# PNP.net
KiCad netlist of a schematic drawn in EAGLE
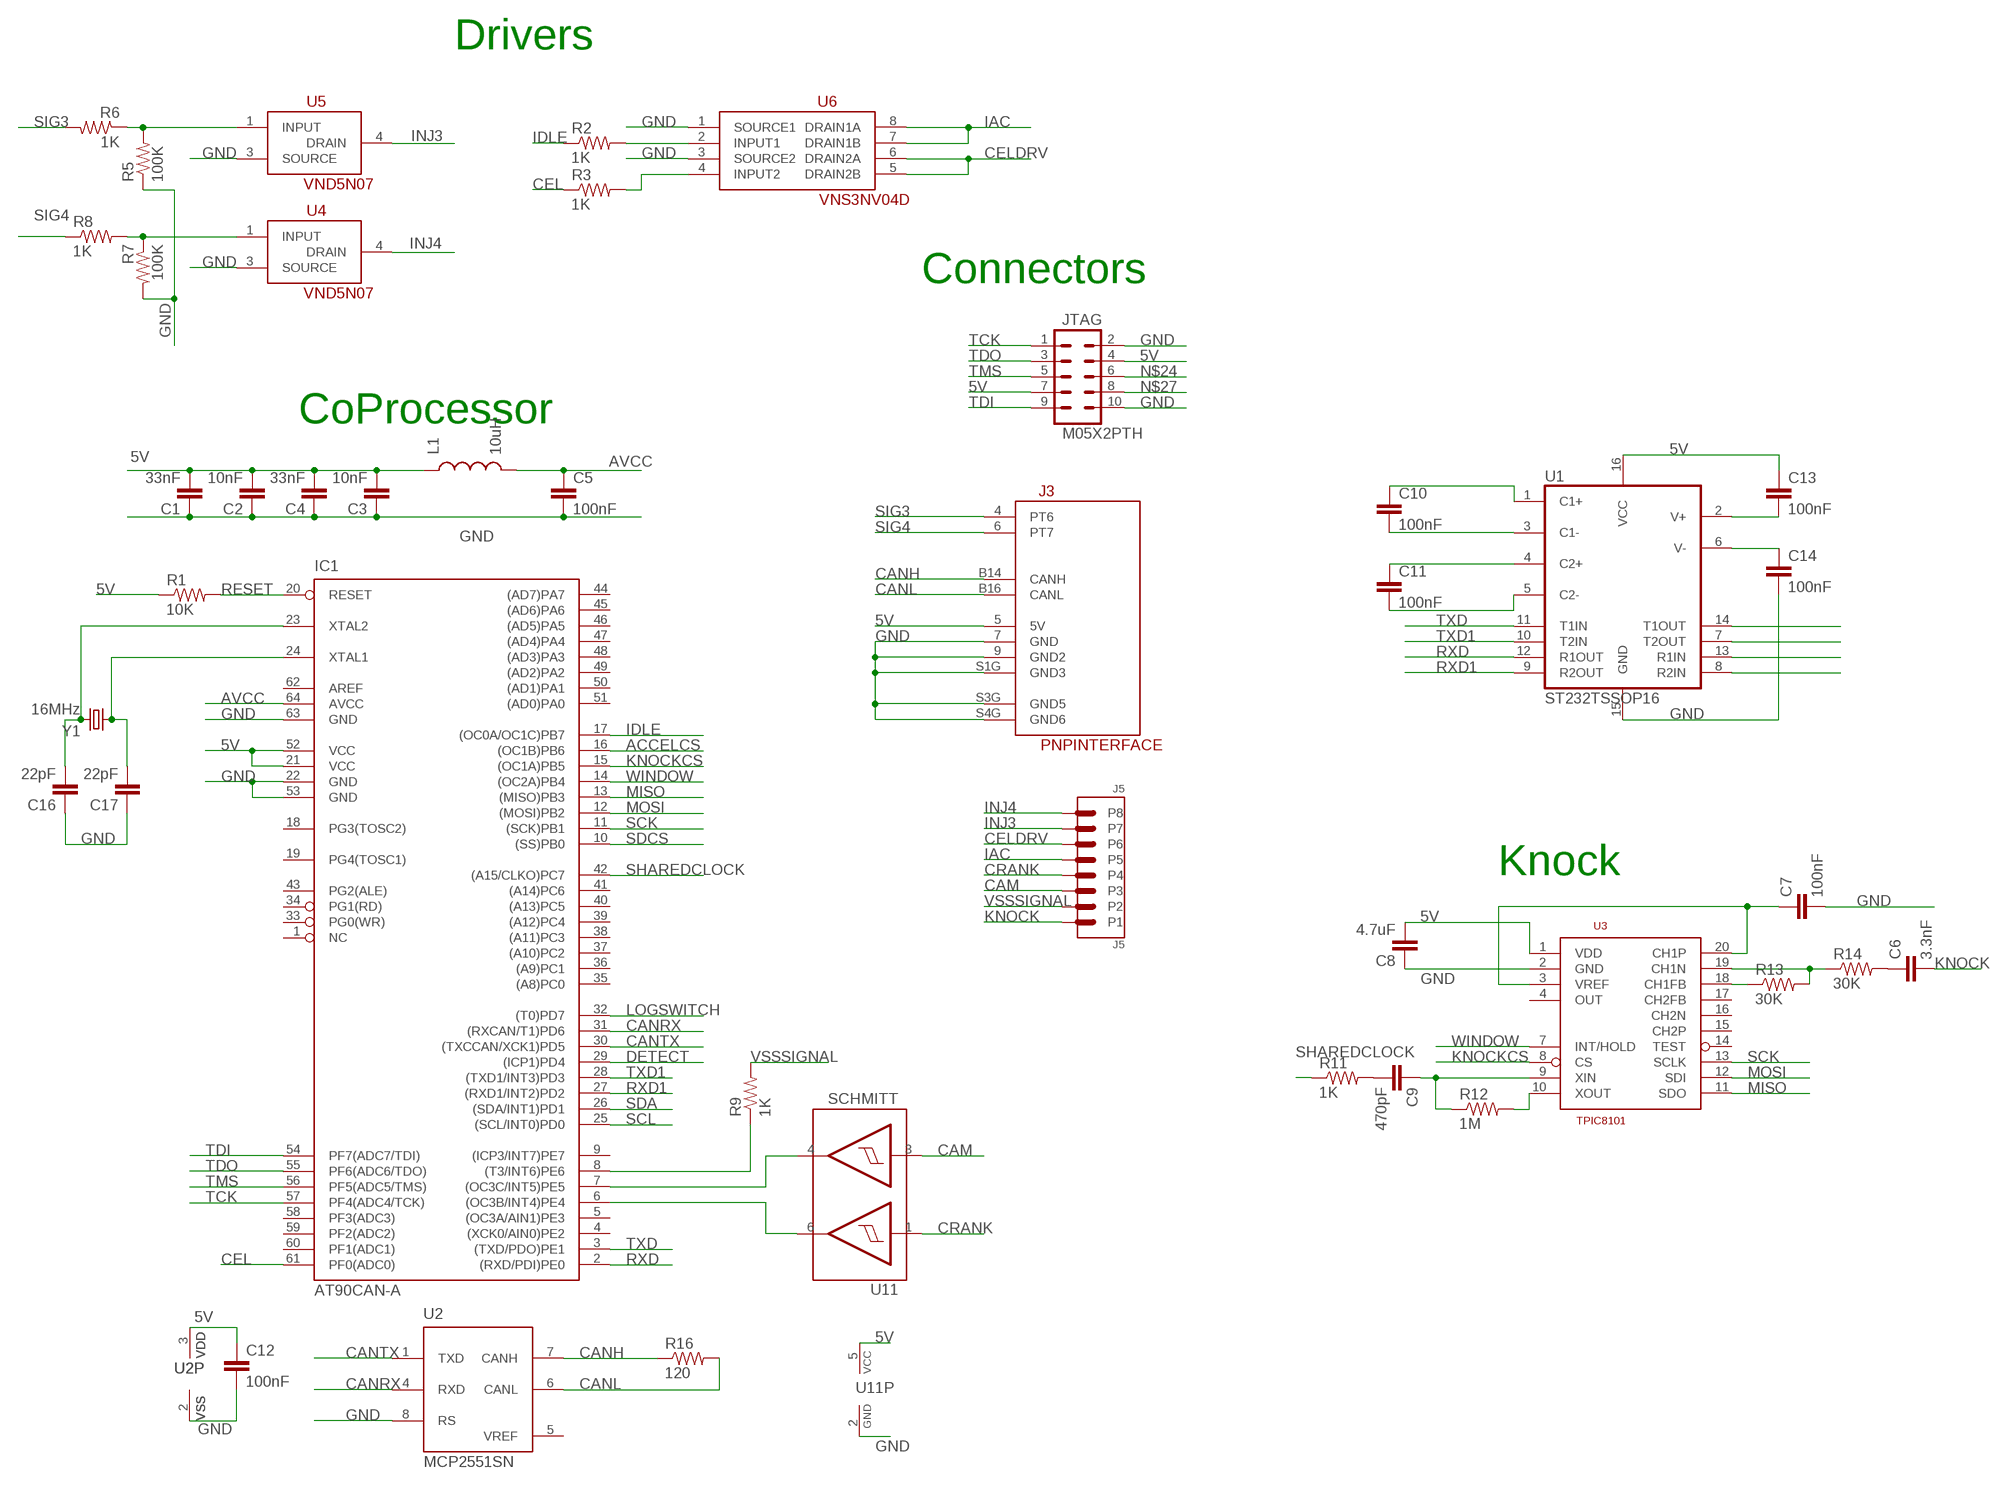
[diagram p0: schematic, sheet 1]

(export (version "E")
  (design (tool "Eeschema 10.0.6"))
  (components
    (comp (ref "C1")
      (value "33nF")
      (footprint "eagle-import:0805")
      (libsource (lib "eagle-import") (part "CAP0805"))
    )
    (comp (ref "C2")
      (value "10nF")
      (footprint "eagle-import:0805")
      (libsource (lib "eagle-import") (part "CAP0805"))
    )
    (comp (ref "C3")
      (value "10nF")
      (footprint "eagle-import:0805")
      (libsource (lib "eagle-import") (part "CAP0805"))
    )
    (comp (ref "C4")
      (value "33nF")
      (footprint "eagle-import:0805")
      (libsource (lib "eagle-import") (part "CAP0805"))
    )
    (comp (ref "C5")
      (value "100nF")
      (footprint "eagle-import:0805")
      (libsource (lib "eagle-import") (part "CAP0805"))
    )
    (comp (ref "C6")
      (value "3.3nF")
      (footprint "eagle-import:0805")
      (libsource (lib "eagle-import") (part "CAP0805"))
    )
    (comp (ref "C7")
      (value "100nF")
      (footprint "eagle-import:0805")
      (libsource (lib "eagle-import") (part "CAP0805"))
    )
    (comp (ref "C8")
      (value "4.7uF")
      (footprint "eagle-import:0805")
      (libsource (lib "eagle-import") (part "CAP0805"))
    )
    (comp (ref "C9")
      (value "470pF")
      (footprint "eagle-import:0805")
      (libsource (lib "eagle-import") (part "CAP0805"))
    )
    (comp (ref "C10")
      (value "100nF")
      (footprint "eagle-import:0805")
      (libsource (lib "eagle-import") (part "CAP0805"))
    )
    (comp (ref "C11")
      (value "100nF")
      (footprint "eagle-import:0805")
      (libsource (lib "eagle-import") (part "CAP0805"))
    )
    (comp (ref "C12")
      (value "100nF")
      (footprint "eagle-import:0805")
      (libsource (lib "eagle-import") (part "CAP0805"))
    )
    (comp (ref "C13")
      (value "100nF")
      (footprint "eagle-import:0805")
      (libsource (lib "eagle-import") (part "CAP0805"))
    )
    (comp (ref "C14")
      (value "100nF")
      (footprint "eagle-import:0805")
      (libsource (lib "eagle-import") (part "CAP0805"))
    )
    (comp (ref "C16")
      (value "22pF")
      (footprint "eagle-import:0805")
      (libsource (lib "eagle-import") (part "CAP0805"))
    )
    (comp (ref "C17")
      (value "22pF")
      (footprint "eagle-import:0805")
      (libsource (lib "eagle-import") (part "CAP0805"))
    )
    (comp (ref "IC1")
      (value "AT90CAN-A")
      (footprint "eagle-import:TQFP64")
      (fields (field (name "MPN") "AT90CAN32-16AU"))
      (libsource (lib "eagle-import") (part "AT90CAN-A"))
    )
    (comp (ref "J3")
      (value "PNPINTERFACE")
      (footprint "eagle-import:PNPBOARD")
      (libsource (lib "eagle-import") (part "PNPINTERFACE"))
    )
    (comp (ref "J5")
      (value "J5")
      (footprint "eagle-import:TERMINAL8")
      (libsource (lib "eagle-import") (part "TERMINAL8"))
    )
    (comp (ref "JTAG")
      (value "M05X2PTH")
      (footprint "eagle-import:AVR_ICSP")
      (libsource (lib "eagle-import") (part "M05X2PTH"))
    )
    (comp (ref "L1")
      (value "10uH")
      (footprint "eagle-import:1210")
      (libsource (lib "eagle-import") (part "INDUCTOR1210"))
    )
    (comp (ref "R1")
      (value "10K")
      (footprint "eagle-import:0805")
      (libsource (lib "eagle-import") (part "RESISTOR0805-RES"))
    )
    (comp (ref "R2")
      (value "1K")
      (footprint "eagle-import:0805")
      (libsource (lib "eagle-import") (part "RESISTOR0805-RES"))
    )
    (comp (ref "R3")
      (value "1K")
      (footprint "eagle-import:0805")
      (libsource (lib "eagle-import") (part "RESISTOR0805-RES"))
    )
    (comp (ref "R5")
      (value "100K")
      (footprint "eagle-import:0805")
      (libsource (lib "eagle-import") (part "RESISTOR0805-RES"))
    )
    (comp (ref "R6")
      (value "1K")
      (footprint "eagle-import:0805")
      (libsource (lib "eagle-import") (part "RESISTOR0805-RES"))
    )
    (comp (ref "R7")
      (value "100K")
      (footprint "eagle-import:0805")
      (libsource (lib "eagle-import") (part "RESISTOR0805-RES"))
    )
    (comp (ref "R8")
      (value "1K")
      (footprint "eagle-import:0805")
      (libsource (lib "eagle-import") (part "RESISTOR0805-RES"))
    )
    (comp (ref "R9")
      (value "1K")
      (footprint "eagle-import:0805")
      (libsource (lib "eagle-import") (part "RESISTOR0805-RES"))
    )
    (comp (ref "R11")
      (value "1K")
      (footprint "eagle-import:0805")
      (libsource (lib "eagle-import") (part "RESISTOR0805-RES"))
    )
    (comp (ref "R12")
      (value "1M")
      (footprint "eagle-import:0805")
      (libsource (lib "eagle-import") (part "RESISTOR0805-RES"))
    )
    (comp (ref "R13")
      (value "30K")
      (footprint "eagle-import:0805")
      (libsource (lib "eagle-import") (part "RESISTOR0805-RES"))
    )
    (comp (ref "R14")
      (value "30K")
      (footprint "eagle-import:0805")
      (libsource (lib "eagle-import") (part "RESISTOR0805-RES"))
    )
    (comp (ref "R16")
      (value "120")
      (footprint "eagle-import:0805")
      (libsource (lib "eagle-import") (part "RESISTOR0805-RES"))
    )
    (comp (ref "U1")
      (value "ST232TSSOP16")
      (footprint "eagle-import:TSSOP16")
      (libsource (lib "eagle-import") (part "ST232TSSOP16"))
    )
    (comp (ref "U2")
      (value "MCP2551SN")
      (footprint "eagle-import:SO8")
      (libsource (lib "eagle-import") (part "MCP2551SN"))
    )
    (comp (ref "U3")
      (value "TPIC8101")
      (footprint "eagle-import:SO-20DW")
      (libsource (lib "eagle-import") (part "TPIC8101"))
    )
    (comp (ref "U4")
      (value "VND5N07")
      (footprint "eagle-import:DPAK")
      (libsource (lib "eagle-import") (part "VND5N07"))
    )
    (comp (ref "U5")
      (value "VND5N07")
      (footprint "eagle-import:DPAK")
      (libsource (lib "eagle-import") (part "VND5N07"))
    )
    (comp (ref "U6")
      (value "VNS3NV04D")
      (footprint "eagle-import:SO8")
      (libsource (lib "eagle-import") (part "VNS3NV04D"))
    )
    (comp (ref "U11")
      (value "SCHMITT")
      (footprint "eagle-import:TSOP6")
      (libsource (lib "eagle-import") (part "SCHMITTTSOP"))
    )
    (comp (ref "Y1")
      (value "16MHz")
      (footprint "eagle-import:SM2-CRYSTAL-7ASERIES")
      (libsource (lib "eagle-import") (part "CRYSTAL"))
    )
  )
  (nets
    (net (code "1") (name "/5V") (class "Default")
      (node (ref "C1") (pin "2") (pinfunction "2_2") (pintype "passive"))
      (node (ref "C12") (pin "1") (pinfunction "1_1") (pintype "passive"))
      (node (ref "C13") (pin "1") (pinfunction "1_1") (pintype "passive"))
      (node (ref "C2") (pin "2") (pinfunction "2_2") (pintype "passive"))
      (node (ref "C3") (pin "2") (pinfunction "2_2") (pintype "passive"))
      (node (ref "C4") (pin "2") (pinfunction "2_2") (pintype "passive"))
      (node (ref "C8") (pin "2") (pinfunction "2_2") (pintype "passive"))
      (node (ref "IC1") (pin "21") (pinfunction "VCC_21") (pintype "power_in"))
      (node (ref "IC1") (pin "52") (pinfunction "VCC_52") (pintype "power_in"))
      (node (ref "J3") (pin "5") (pinfunction "5V_5") (pintype "power_in"))
      (node (ref "JTAG") (pin "4") (pinfunction "4_4") (pintype "passive"))
      (node (ref "JTAG") (pin "7") (pinfunction "7_7") (pintype "passive"))
      (node (ref "L1") (pin "1") (pinfunction "1_1") (pintype "passive"))
      (node (ref "R1") (pin "1") (pinfunction "1_1") (pintype "passive"))
      (node (ref "U1") (pin "16") (pinfunction "VCC_16") (pintype "bidirectional"))
      (node (ref "U11") (pin "5") (pinfunction "VCC_5") (pintype "power_in"))
      (node (ref "U2") (pin "3") (pinfunction "VDD_3") (pintype "power_in"))
      (node (ref "U3") (pin "1") (pinfunction "VDD_1") (pintype "power_in"))
    )
    (net (code "2") (name "/ACCELCS") (class "Default")
      (node (ref "IC1") (pin "16") (pinfunction "(OC1B)PB6_16") (pintype "bidirectional"))
    )
    (net (code "3") (name "/AVCC") (class "Default")
      (node (ref "C5") (pin "1") (pinfunction "1_1") (pintype "passive"))
      (node (ref "IC1") (pin "64") (pinfunction "AVCC_64") (pintype "power_in"))
      (node (ref "L1") (pin "2") (pinfunction "2_2") (pintype "passive"))
    )
    (net (code "4") (name "/CAM") (class "Default")
      (node (ref "J5") (pin "P3") (pinfunction "P3_P3") (pintype "passive"))
      (node (ref "U11") (pin "3") (pinfunction "I2_3") (pintype "input"))
    )
    (net (code "5") (name "/CANH") (class "Default")
      (node (ref "J3") (pin "B14") (pinfunction "CANH_B14") (pintype "bidirectional"))
      (node (ref "R16") (pin "1") (pinfunction "1_1") (pintype "passive"))
      (node (ref "U2") (pin "7") (pinfunction "CANH_7") (pintype "bidirectional"))
    )
    (net (code "6") (name "/CANL") (class "Default")
      (node (ref "J3") (pin "B16") (pinfunction "CANL_B16") (pintype "bidirectional"))
      (node (ref "R16") (pin "2") (pinfunction "2_2") (pintype "passive"))
      (node (ref "U2") (pin "6") (pinfunction "CANL_6") (pintype "bidirectional"))
    )
    (net (code "7") (name "/CANRX") (class "Default")
      (node (ref "IC1") (pin "31") (pinfunction "(RXCAN/T1)PD6_31") (pintype "bidirectional"))
      (node (ref "U2") (pin "4") (pinfunction "RXD_4") (pintype "output"))
    )
    (net (code "8") (name "/CANTX") (class "Default")
      (node (ref "IC1") (pin "30") (pinfunction "(TXCCAN/XCK1)PD5_30") (pintype "bidirectional"))
      (node (ref "U2") (pin "1") (pinfunction "TXD_1") (pintype "input"))
    )
    (net (code "9") (name "/CEL") (class "Default")
      (node (ref "IC1") (pin "61") (pinfunction "PF0(ADC0)_61") (pintype "bidirectional"))
      (node (ref "R3") (pin "1") (pinfunction "1_1") (pintype "passive"))
    )
    (net (code "10") (name "/CELDRV") (class "Default")
      (node (ref "J5") (pin "P6") (pinfunction "P6_P6") (pintype "passive"))
      (node (ref "U6") (pin "5") (pinfunction "DRAIN2B_5") (pintype "bidirectional"))
      (node (ref "U6") (pin "6") (pinfunction "DRAIN2A_6") (pintype "bidirectional"))
    )
    (net (code "11") (name "/CRANK") (class "Default")
      (node (ref "J5") (pin "P4") (pinfunction "P4_P4") (pintype "passive"))
      (node (ref "U11") (pin "1") (pinfunction "I1_1") (pintype "input"))
    )
    (net (code "12") (name "/DETECT") (class "Default")
      (node (ref "IC1") (pin "29") (pinfunction "(ICP1)PD4_29") (pintype "bidirectional"))
    )
    (net (code "13") (name "/GND") (class "Default")
      (node (ref "C1") (pin "1") (pinfunction "1_1") (pintype "passive"))
      (node (ref "C12") (pin "2") (pinfunction "2_2") (pintype "passive"))
      (node (ref "C14") (pin "2") (pinfunction "2_2") (pintype "passive"))
      (node (ref "C16") (pin "1") (pinfunction "1_1") (pintype "passive"))
      (node (ref "C17") (pin "1") (pinfunction "1_1") (pintype "passive"))
      (node (ref "C2") (pin "1") (pinfunction "1_1") (pintype "passive"))
      (node (ref "C3") (pin "1") (pinfunction "1_1") (pintype "passive"))
      (node (ref "C4") (pin "1") (pinfunction "1_1") (pintype "passive"))
      (node (ref "C5") (pin "2") (pinfunction "2_2") (pintype "passive"))
      (node (ref "C7") (pin "2") (pinfunction "2_2") (pintype "passive"))
      (node (ref "C8") (pin "1") (pinfunction "1_1") (pintype "passive"))
      (node (ref "IC1") (pin "22") (pinfunction "GND_22") (pintype "power_in"))
      (node (ref "IC1") (pin "53") (pinfunction "GND_53") (pintype "power_in"))
      (node (ref "IC1") (pin "63") (pinfunction "GND_63") (pintype "power_in"))
      (node (ref "J3") (pin "7") (pinfunction "GND_7") (pintype "power_in"))
      (node (ref "J3") (pin "9") (pinfunction "GND2_9") (pintype "passive"))
      (node (ref "J3") (pin "S1G") (pinfunction "GND3_S1G") (pintype "passive"))
      (node (ref "J3") (pin "S3G") (pinfunction "GND5_S3G") (pintype "passive"))
      (node (ref "J3") (pin "S4G") (pinfunction "GND6_S4G") (pintype "passive"))
      (node (ref "JTAG") (pin "10") (pinfunction "10_10") (pintype "passive"))
      (node (ref "JTAG") (pin "2") (pinfunction "2_2") (pintype "passive"))
      (node (ref "R5") (pin "1") (pinfunction "1_1") (pintype "passive"))
      (node (ref "R7") (pin "2") (pinfunction "2_2") (pintype "passive"))
      (node (ref "U1") (pin "15") (pinfunction "GND_15") (pintype "bidirectional"))
      (node (ref "U11") (pin "2") (pinfunction "GND_2") (pintype "power_in"))
      (node (ref "U2") (pin "2") (pinfunction "VSS_2") (pintype "power_in"))
      (node (ref "U2") (pin "8") (pinfunction "RS_8") (pintype "input"))
      (node (ref "U3") (pin "2") (pinfunction "GND_2") (pintype "power_in"))
      (node (ref "U4") (pin "3") (pinfunction "SOURCE_3") (pintype "bidirectional"))
      (node (ref "U5") (pin "3") (pinfunction "SOURCE_3") (pintype "bidirectional"))
      (node (ref "U6") (pin "1") (pinfunction "SOURCE1_1") (pintype "bidirectional"))
      (node (ref "U6") (pin "3") (pinfunction "SOURCE2_3") (pintype "bidirectional"))
    )
    (net (code "14") (name "/IAC") (class "Default")
      (node (ref "J5") (pin "P5") (pinfunction "P5_P5") (pintype "passive"))
      (node (ref "U6") (pin "7") (pinfunction "DRAIN1B_7") (pintype "bidirectional"))
      (node (ref "U6") (pin "8") (pinfunction "DRAIN1A_8") (pintype "bidirectional"))
    )
    (net (code "15") (name "/IDLE") (class "Default")
      (node (ref "IC1") (pin "17") (pinfunction "(OC0A/OC1C)PB7_17") (pintype "bidirectional"))
      (node (ref "R2") (pin "1") (pinfunction "1_1") (pintype "passive"))
    )
    (net (code "16") (name "/INJ3") (class "Default")
      (node (ref "J5") (pin "P7") (pinfunction "P7_P7") (pintype "passive"))
      (node (ref "U5") (pin "4") (pinfunction "DRAIN_4") (pintype "bidirectional"))
    )
    (net (code "17") (name "/INJ4") (class "Default")
      (node (ref "J5") (pin "P8") (pinfunction "P8_P8") (pintype "passive"))
      (node (ref "U4") (pin "4") (pinfunction "DRAIN_4") (pintype "bidirectional"))
    )
    (net (code "18") (name "/KNOCK") (class "Default")
      (node (ref "C6") (pin "2") (pinfunction "2_2") (pintype "passive"))
      (node (ref "J5") (pin "P1") (pinfunction "P1_P1") (pintype "passive"))
    )
    (net (code "19") (name "/KNOCKCS") (class "Default")
      (node (ref "IC1") (pin "15") (pinfunction "(OC1A)PB5_15") (pintype "bidirectional"))
      (node (ref "U3") (pin "8") (pinfunction "CS_8") (pintype "input"))
    )
    (net (code "20") (name "/LOGSWITCH") (class "Default")
      (node (ref "IC1") (pin "32") (pinfunction "(T0)PD7_32") (pintype "bidirectional"))
    )
    (net (code "21") (name "/MISO") (class "Default")
      (node (ref "IC1") (pin "13") (pinfunction "(MISO)PB3_13") (pintype "bidirectional"))
      (node (ref "U3") (pin "11") (pinfunction "SDO_11") (pintype "bidirectional"))
    )
    (net (code "22") (name "/MOSI") (class "Default")
      (node (ref "IC1") (pin "12") (pinfunction "(MOSI)PB2_12") (pintype "bidirectional"))
      (node (ref "U3") (pin "12") (pinfunction "SDI_12") (pintype "input"))
    )
    (net (code "23") (name "/N$24") (class "Default")
      (node (ref "JTAG") (pin "6") (pinfunction "6_6") (pintype "passive"))
    )
    (net (code "24") (name "/N$27") (class "Default")
      (node (ref "JTAG") (pin "8") (pinfunction "8_8") (pintype "passive"))
    )
    (net (code "25") (name "/RESET") (class "Default")
      (node (ref "IC1") (pin "20") (pinfunction "RESET_20") (pintype "input"))
      (node (ref "R1") (pin "2") (pinfunction "2_2") (pintype "passive"))
    )
    (net (code "26") (name "/RXD") (class "Default")
      (node (ref "IC1") (pin "2") (pinfunction "(RXD/PDI)PE0_2") (pintype "bidirectional"))
      (node (ref "U1") (pin "12") (pinfunction "R1OUT_12") (pintype "output"))
    )
    (net (code "27") (name "/RXD1") (class "Default")
      (node (ref "IC1") (pin "27") (pinfunction "(RXD1/INT2)PD2_27") (pintype "bidirectional"))
      (node (ref "U1") (pin "9") (pinfunction "R2OUT_9") (pintype "output"))
    )
    (net (code "28") (name "/SCK") (class "Default")
      (node (ref "IC1") (pin "11") (pinfunction "(SCK)PB1_11") (pintype "bidirectional"))
      (node (ref "U3") (pin "13") (pinfunction "SCLK_13") (pintype "input"))
    )
    (net (code "29") (name "/SCL") (class "Default")
      (node (ref "IC1") (pin "25") (pinfunction "(SCL/INT0)PD0_25") (pintype "bidirectional"))
    )
    (net (code "30") (name "/SDA") (class "Default")
      (node (ref "IC1") (pin "26") (pinfunction "(SDA/INT1)PD1_26") (pintype "bidirectional"))
    )
    (net (code "31") (name "/SDCS") (class "Default")
      (node (ref "IC1") (pin "10") (pinfunction "(SS)PB0_10") (pintype "bidirectional"))
    )
    (net (code "32") (name "/SHAREDCLOCK") (class "Default")
      (node (ref "IC1") (pin "42") (pinfunction "(A15/CLKO)PC7_42") (pintype "output"))
      (node (ref "R11") (pin "1") (pinfunction "1_1") (pintype "passive"))
    )
    (net (code "33") (name "/SIG3") (class "Default")
      (node (ref "J3") (pin "4") (pinfunction "PT6_4") (pintype "input"))
      (node (ref "R6") (pin "2") (pinfunction "2_2") (pintype "passive"))
    )
    (net (code "34") (name "/SIG4") (class "Default")
      (node (ref "J3") (pin "6") (pinfunction "PT7_6") (pintype "input"))
      (node (ref "R8") (pin "1") (pinfunction "1_1") (pintype "passive"))
    )
    (net (code "35") (name "/TCK") (class "Default")
      (node (ref "IC1") (pin "57") (pinfunction "PF4(ADC4/TCK)_57") (pintype "bidirectional"))
      (node (ref "JTAG") (pin "1") (pinfunction "1_1") (pintype "passive"))
    )
    (net (code "36") (name "/TDI") (class "Default")
      (node (ref "IC1") (pin "54") (pinfunction "PF7(ADC7/TDI)_54") (pintype "bidirectional"))
      (node (ref "JTAG") (pin "9") (pinfunction "9_9") (pintype "passive"))
    )
    (net (code "37") (name "/TDO") (class "Default")
      (node (ref "IC1") (pin "55") (pinfunction "PF6(ADC6/TDO)_55") (pintype "bidirectional"))
      (node (ref "JTAG") (pin "3") (pinfunction "3_3") (pintype "passive"))
    )
    (net (code "38") (name "/TMS") (class "Default")
      (node (ref "IC1") (pin "56") (pinfunction "PF5(ADC5/TMS)_56") (pintype "bidirectional"))
      (node (ref "JTAG") (pin "5") (pinfunction "5_5") (pintype "passive"))
    )
    (net (code "39") (name "/TXD") (class "Default")
      (node (ref "IC1") (pin "3") (pinfunction "(TXD/PDO)PE1_3") (pintype "bidirectional"))
      (node (ref "U1") (pin "11") (pinfunction "T1IN_11") (pintype "input"))
    )
    (net (code "40") (name "/TXD1") (class "Default")
      (node (ref "IC1") (pin "28") (pinfunction "(TXD1/INT3)PD3_28") (pintype "bidirectional"))
      (node (ref "U1") (pin "10") (pinfunction "T2IN_10") (pintype "input"))
    )
    (net (code "41") (name "/VSSSIGNAL") (class "Default")
      (node (ref "J5") (pin "P2") (pinfunction "P2_P2") (pintype "passive"))
      (node (ref "R9") (pin "2") (pinfunction "2_2") (pintype "passive"))
    )
    (net (code "42") (name "/WINDOW") (class "Default")
      (node (ref "IC1") (pin "14") (pinfunction "(OC2A)PB4_14") (pintype "bidirectional"))
      (node (ref "U3") (pin "7") (pinfunction "INT/HOLD_7") (pintype "bidirectional"))
    )
    (net (code "43") (name "Net-(C6-Pad1)") (class "Default")
      (node (ref "C6") (pin "1") (pinfunction "1_1") (pintype "passive"))
      (node (ref "R14") (pin "2") (pinfunction "2_2") (pintype "passive"))
    )
    (net (code "44") (name "Net-(C9-Pad2)") (class "Default")
      (node (ref "C9") (pin "2") (pinfunction "2_2") (pintype "passive"))
      (node (ref "R11") (pin "2") (pinfunction "2_2") (pintype "passive"))
    )
    (net (code "45") (name "Net-(IC1-(OC3B{slash}INT4)PE4)") (class "Default")
      (node (ref "IC1") (pin "6") (pinfunction "(OC3B/INT4)PE4_6") (pintype "bidirectional"))
      (node (ref "U11") (pin "6") (pinfunction "O1_6") (pintype "output"))
    )
    (net (code "46") (name "Net-(IC1-(OC3C{slash}INT5)PE5)") (class "Default")
      (node (ref "IC1") (pin "7") (pinfunction "(OC3C/INT5)PE5_7") (pintype "bidirectional"))
      (node (ref "U11") (pin "4") (pinfunction "O2_4") (pintype "output"))
    )
    (net (code "47") (name "Net-(IC1-(T3{slash}INT6)PE6)") (class "Default")
      (node (ref "IC1") (pin "8") (pinfunction "(T3/INT6)PE6_8") (pintype "bidirectional"))
      (node (ref "R9") (pin "1") (pinfunction "1_1") (pintype "passive"))
    )
    (net (code "48") (name "Net-(IC1-XTAL1)") (class "Default")
      (node (ref "C17") (pin "2") (pinfunction "2_2") (pintype "passive"))
      (node (ref "IC1") (pin "24") (pinfunction "XTAL1_24") (pintype "bidirectional"))
      (node (ref "Y1") (pin "P$1") (pinfunction "1_P$1") (pintype "passive"))
    )
    (net (code "49") (name "Net-(IC1-XTAL2)") (class "Default")
      (node (ref "C16") (pin "2") (pinfunction "2_2") (pintype "passive"))
      (node (ref "IC1") (pin "23") (pinfunction "XTAL2_23") (pintype "bidirectional"))
      (node (ref "Y1") (pin "P$2") (pinfunction "2_P$2") (pintype "passive"))
    )
    (net (code "50") (name "Net-(U1-C1+)") (class "Default")
      (node (ref "C10") (pin "1") (pinfunction "1_1") (pintype "passive"))
      (node (ref "U1") (pin "1") (pinfunction "C1+_1") (pintype "bidirectional"))
    )
    (net (code "51") (name "Net-(U1-C1-)") (class "Default")
      (node (ref "C10") (pin "2") (pinfunction "2_2") (pintype "passive"))
      (node (ref "U1") (pin "3") (pinfunction "C1-_3") (pintype "bidirectional"))
    )
    (net (code "52") (name "Net-(U1-C2+)") (class "Default")
      (node (ref "C11") (pin "1") (pinfunction "1_1") (pintype "passive"))
      (node (ref "U1") (pin "4") (pinfunction "C2+_4") (pintype "bidirectional"))
    )
    (net (code "53") (name "Net-(U1-C2-)") (class "Default")
      (node (ref "C11") (pin "2") (pinfunction "2_2") (pintype "passive"))
      (node (ref "U1") (pin "5") (pinfunction "C2-_5") (pintype "bidirectional"))
    )
    (net (code "54") (name "Net-(U1-V+)") (class "Default")
      (node (ref "C13") (pin "2") (pinfunction "2_2") (pintype "passive"))
      (node (ref "U1") (pin "2") (pinfunction "V+_2") (pintype "bidirectional"))
    )
    (net (code "55") (name "Net-(U1-V-)") (class "Default")
      (node (ref "C14") (pin "1") (pinfunction "1_1") (pintype "passive"))
      (node (ref "U1") (pin "6") (pinfunction "V-_6") (pintype "bidirectional"))
    )
    (net (code "56") (name "Net-(U3-CH1FB)") (class "Default")
      (node (ref "R13") (pin "1") (pinfunction "1_1") (pintype "passive"))
      (node (ref "U3") (pin "18") (pinfunction "CH1FB_18") (pintype "bidirectional"))
    )
    (net (code "57") (name "Net-(U3-CH1N)") (class "Default")
      (node (ref "R13") (pin "2") (pinfunction "2_2") (pintype "passive"))
      (node (ref "R14") (pin "1") (pinfunction "1_1") (pintype "passive"))
      (node (ref "U3") (pin "19") (pinfunction "CH1N_19") (pintype "bidirectional"))
    )
    (net (code "58") (name "Net-(U3-CH1P)") (class "Default")
      (node (ref "C7") (pin "1") (pinfunction "1_1") (pintype "passive"))
      (node (ref "U3") (pin "20") (pinfunction "CH1P_20") (pintype "bidirectional"))
      (node (ref "U3") (pin "3") (pinfunction "VREF_3") (pintype "passive"))
    )
    (net (code "59") (name "Net-(U3-XIN)") (class "Default")
      (node (ref "C9") (pin "1") (pinfunction "1_1") (pintype "passive"))
      (node (ref "R12") (pin "1") (pinfunction "1_1") (pintype "passive"))
      (node (ref "U3") (pin "9") (pinfunction "XIN_9") (pintype "passive"))
    )
    (net (code "60") (name "Net-(U3-XOUT)") (class "Default")
      (node (ref "R12") (pin "2") (pinfunction "2_2") (pintype "passive"))
      (node (ref "U3") (pin "10") (pinfunction "XOUT_10") (pintype "passive"))
    )
    (net (code "61") (name "Net-(U4-INPUT)") (class "Default")
      (node (ref "R7") (pin "1") (pinfunction "1_1") (pintype "passive"))
      (node (ref "R8") (pin "2") (pinfunction "2_2") (pintype "passive"))
      (node (ref "U4") (pin "1") (pinfunction "INPUT_1") (pintype "input"))
    )
    (net (code "62") (name "Net-(U5-INPUT)") (class "Default")
      (node (ref "R5") (pin "2") (pinfunction "2_2") (pintype "passive"))
      (node (ref "R6") (pin "1") (pinfunction "1_1") (pintype "passive"))
      (node (ref "U5") (pin "1") (pinfunction "INPUT_1") (pintype "input"))
    )
    (net (code "63") (name "Net-(U6-INPUT1)") (class "Default")
      (node (ref "R2") (pin "2") (pinfunction "2_2") (pintype "passive"))
      (node (ref "U6") (pin "2") (pinfunction "INPUT1_2") (pintype "input"))
    )
    (net (code "64") (name "Net-(U6-INPUT2)") (class "Default")
      (node (ref "R3") (pin "2") (pinfunction "2_2") (pintype "passive"))
      (node (ref "U6") (pin "4") (pinfunction "INPUT2_4") (pintype "input"))
    )
    (net (code "65") (name "unconnected-(IC1-(A8)PC0-Pad35)") (class "Default")
      (node (ref "IC1") (pin "35") (pinfunction "(A8)PC0_35") (pintype "output"))
    )
    (net (code "66") (name "unconnected-(IC1-(A9)PC1-Pad36)") (class "Default")
      (node (ref "IC1") (pin "36") (pinfunction "(A9)PC1_36") (pintype "output"))
    )
    (net (code "67") (name "unconnected-(IC1-(A10)PC2-Pad37)") (class "Default")
      (node (ref "IC1") (pin "37") (pinfunction "(A10)PC2_37") (pintype "output"))
    )
    (net (code "68") (name "unconnected-(IC1-(A11)PC3-Pad38)") (class "Default")
      (node (ref "IC1") (pin "38") (pinfunction "(A11)PC3_38") (pintype "output"))
    )
    (net (code "69") (name "unconnected-(IC1-(A12)PC4-Pad39)") (class "Default")
      (node (ref "IC1") (pin "39") (pinfunction "(A12)PC4_39") (pintype "output"))
    )
    (net (code "70") (name "unconnected-(IC1-(A13)PC5-Pad40)") (class "Default")
      (node (ref "IC1") (pin "40") (pinfunction "(A13)PC5_40") (pintype "output"))
    )
    (net (code "71") (name "unconnected-(IC1-(A14)PC6-Pad41)") (class "Default")
      (node (ref "IC1") (pin "41") (pinfunction "(A14)PC6_41") (pintype "output"))
    )
    (net (code "72") (name "unconnected-(IC1-(AD0)PA0-Pad51)") (class "Default")
      (node (ref "IC1") (pin "51") (pinfunction "(AD0)PA0_51") (pintype "bidirectional"))
    )
    (net (code "73") (name "unconnected-(IC1-(AD1)PA1-Pad50)") (class "Default")
      (node (ref "IC1") (pin "50") (pinfunction "(AD1)PA1_50") (pintype "bidirectional"))
    )
    (net (code "74") (name "unconnected-(IC1-(AD2)PA2-Pad49)") (class "Default")
      (node (ref "IC1") (pin "49") (pinfunction "(AD2)PA2_49") (pintype "bidirectional"))
    )
    (net (code "75") (name "unconnected-(IC1-(AD3)PA3-Pad48)") (class "Default")
      (node (ref "IC1") (pin "48") (pinfunction "(AD3)PA3_48") (pintype "bidirectional"))
    )
    (net (code "76") (name "unconnected-(IC1-(AD4)PA4-Pad47)") (class "Default")
      (node (ref "IC1") (pin "47") (pinfunction "(AD4)PA4_47") (pintype "bidirectional"))
    )
    (net (code "77") (name "unconnected-(IC1-(AD5)PA5-Pad46)") (class "Default")
      (node (ref "IC1") (pin "46") (pinfunction "(AD5)PA5_46") (pintype "bidirectional"))
    )
    (net (code "78") (name "unconnected-(IC1-(AD6)PA6-Pad45)") (class "Default")
      (node (ref "IC1") (pin "45") (pinfunction "(AD6)PA6_45") (pintype "bidirectional"))
    )
    (net (code "79") (name "unconnected-(IC1-(AD7)PA7-Pad44)") (class "Default")
      (node (ref "IC1") (pin "44") (pinfunction "(AD7)PA7_44") (pintype "bidirectional"))
    )
    (net (code "80") (name "unconnected-(IC1-(ICP3{slash}INT7)PE7-Pad9)") (class "Default")
      (node (ref "IC1") (pin "9") (pinfunction "(ICP3/INT7)PE7_9") (pintype "bidirectional"))
    )
    (net (code "81") (name "unconnected-(IC1-(OC3A{slash}AIN1)PE3-Pad5)") (class "Default")
      (node (ref "IC1") (pin "5") (pinfunction "(OC3A/AIN1)PE3_5") (pintype "bidirectional"))
    )
    (net (code "82") (name "unconnected-(IC1-(XCK0{slash}AIN0)PE2-Pad4)") (class "Default")
      (node (ref "IC1") (pin "4") (pinfunction "(XCK0/AIN0)PE2_4") (pintype "bidirectional"))
    )
    (net (code "83") (name "unconnected-(IC1-AREF-Pad62)") (class "Default")
      (node (ref "IC1") (pin "62") (pinfunction "AREF_62") (pintype "passive"))
    )
    (net (code "84") (name "unconnected-(IC1-NC-Pad1)") (class "Default")
      (node (ref "IC1") (pin "1") (pinfunction "NC_1") (pintype "no_connect"))
    )
    (net (code "85") (name "unconnected-(IC1-PF1(ADC1)-Pad60)") (class "Default")
      (node (ref "IC1") (pin "60") (pinfunction "PF1(ADC1)_60") (pintype "bidirectional"))
    )
    (net (code "86") (name "unconnected-(IC1-PF2(ADC2)-Pad59)") (class "Default")
      (node (ref "IC1") (pin "59") (pinfunction "PF2(ADC2)_59") (pintype "bidirectional"))
    )
    (net (code "87") (name "unconnected-(IC1-PF3(ADC3)-Pad58)") (class "Default")
      (node (ref "IC1") (pin "58") (pinfunction "PF3(ADC3)_58") (pintype "bidirectional"))
    )
    (net (code "88") (name "unconnected-(IC1-PG0(WR)-Pad33)") (class "Default")
      (node (ref "IC1") (pin "33") (pinfunction "PG0(WR)_33") (pintype "bidirectional"))
    )
    (net (code "89") (name "unconnected-(IC1-PG1(RD)-Pad34)") (class "Default")
      (node (ref "IC1") (pin "34") (pinfunction "PG1(RD)_34") (pintype "bidirectional"))
    )
    (net (code "90") (name "unconnected-(IC1-PG2(ALE)-Pad43)") (class "Default")
      (node (ref "IC1") (pin "43") (pinfunction "PG2(ALE)_43") (pintype "bidirectional"))
    )
    (net (code "91") (name "unconnected-(IC1-PG3(TOSC2)-Pad18)") (class "Default")
      (node (ref "IC1") (pin "18") (pinfunction "PG3(TOSC2)_18") (pintype "bidirectional"))
    )
    (net (code "92") (name "unconnected-(IC1-PG4(TOSC1)-Pad19)") (class "Default")
      (node (ref "IC1") (pin "19") (pinfunction "PG4(TOSC1)_19") (pintype "bidirectional"))
    )
    (net (code "93") (name "unconnected-(U1-R1IN-Pad13)") (class "Default")
      (node (ref "U1") (pin "13") (pinfunction "R1IN_13") (pintype "input"))
    )
    (net (code "94") (name "unconnected-(U1-R2IN-Pad8)") (class "Default")
      (node (ref "U1") (pin "8") (pinfunction "R2IN_8") (pintype "input"))
    )
    (net (code "95") (name "unconnected-(U1-T1OUT-Pad14)") (class "Default")
      (node (ref "U1") (pin "14") (pinfunction "T1OUT_14") (pintype "output"))
    )
    (net (code "96") (name "unconnected-(U1-T2OUT-Pad7)") (class "Default")
      (node (ref "U1") (pin "7") (pinfunction "T2OUT_7") (pintype "output"))
    )
    (net (code "97") (name "unconnected-(U2A-VREF-Pad5)") (class "Default")
      (node (ref "U2") (pin "5") (pinfunction "VREF_5") (pintype "passive"))
    )
    (net (code "98") (name "unconnected-(U3-CH2FB-Pad17)") (class "Default")
      (node (ref "U3") (pin "17") (pinfunction "CH2FB_17") (pintype "bidirectional"))
    )
    (net (code "99") (name "unconnected-(U3-CH2N-Pad16)") (class "Default")
      (node (ref "U3") (pin "16") (pinfunction "CH2N_16") (pintype "bidirectional"))
    )
    (net (code "100") (name "unconnected-(U3-CH2P-Pad15)") (class "Default")
      (node (ref "U3") (pin "15") (pinfunction "CH2P_15") (pintype "bidirectional"))
    )
    (net (code "101") (name "unconnected-(U3-OUT-Pad4)") (class "Default")
      (node (ref "U3") (pin "4") (pinfunction "OUT_4") (pintype "output"))
    )
    (net (code "102") (name "unconnected-(U3-TEST-Pad14)") (class "Default")
      (node (ref "U3") (pin "14") (pinfunction "TEST_14") (pintype "bidirectional"))
    )
  )
)
